# Mach_dieu_khien_tu_xa.net
KiCad netlist of a schematic drawn in Altium Designer
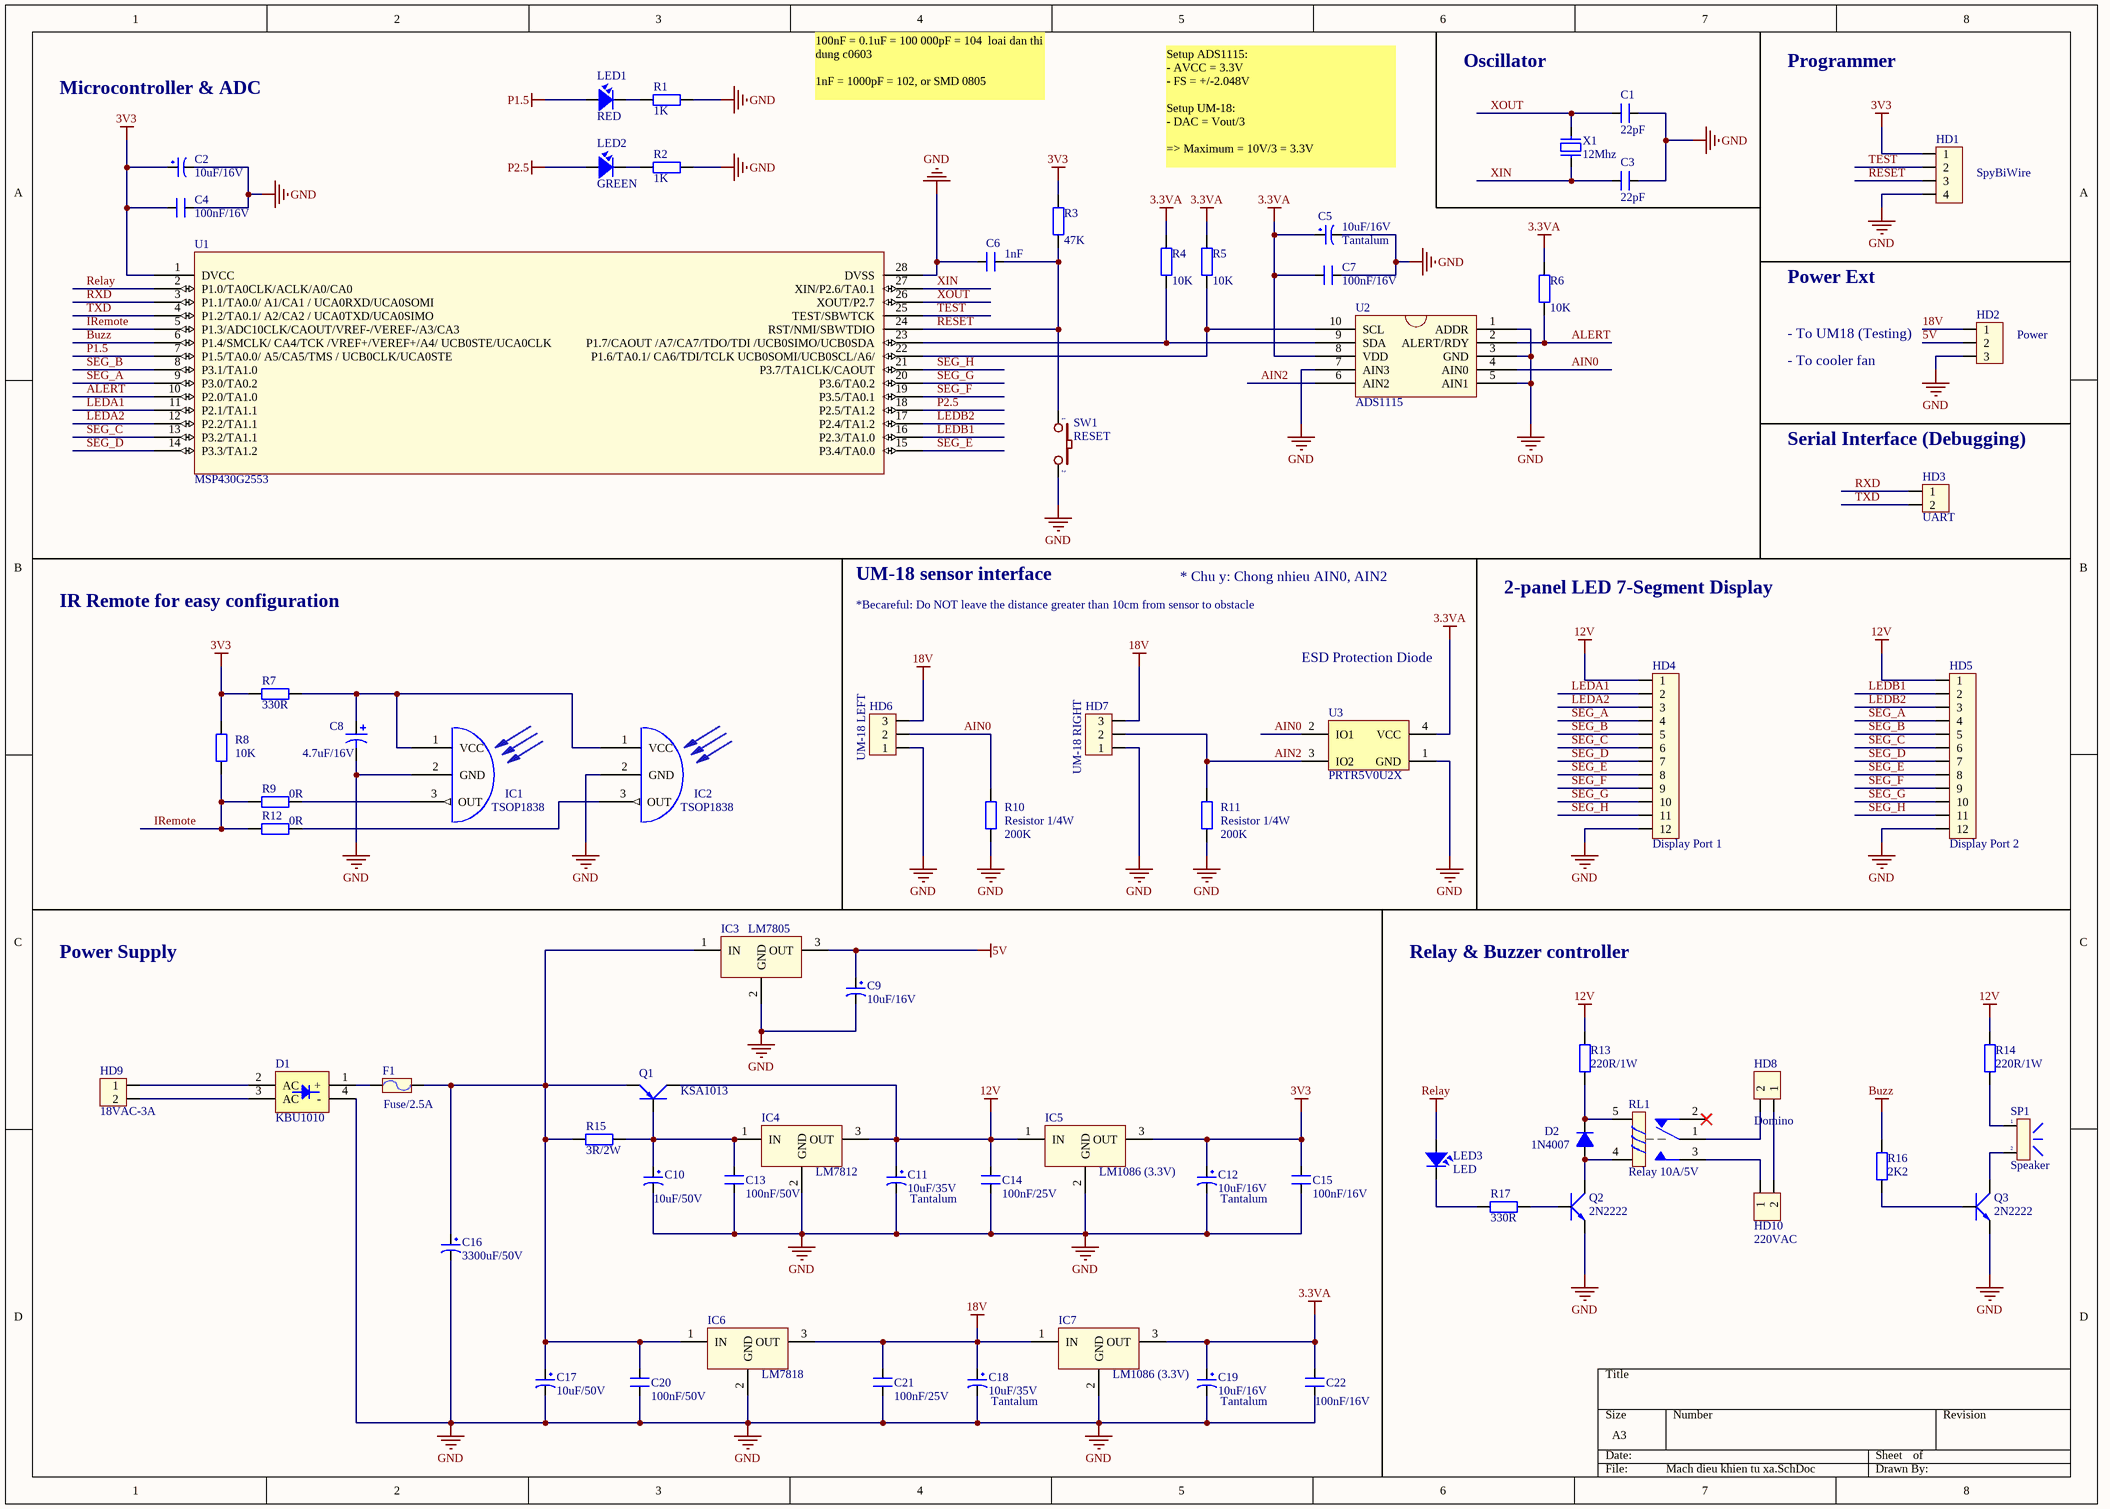
[diagram p0: Mach dieu khien tu xa.SchDoc]

(export (version "E")
  (design (tool "Eeschema 10.0.6"))
  (components
    (comp (ref "C1")
      (value "22pF")
      (footprint "C0603")
      (description "0805-SMD Capacitor")
      (libsource (lib "syhaunguyen") (part "CN1"))
    )
    (comp (ref "C2")
      (value "10uF/16V")
      (footprint "C0805")
      (description "Cap P  0,1uF < 22uF , 16 - 50V")
      (libsource (lib "") (part "CP1_1"))
    )
    (comp (ref "C3")
      (value "22pF")
      (footprint "C0603")
      (description "0805-SMD Capacitor")
      (libsource (lib "syhaunguyen") (part "CN1"))
    )
    (comp (ref "C4")
      (value "100nF/16V")
      (footprint "Tu gom 104")
      (description "Cap np 104 => 105pF")
      (libsource (lib "VNELEK") (part "CN2"))
    )
    (comp (ref "C5")
      (value "10uF/16V")
      (footprint "CAP_TANTA_10UF_16V")
      (description "Tantalum Capacitor")
      (fields (field (name "TYPE") "Tantalum"))
      (libsource (lib "") (part "CP1_1"))
    )
    (comp (ref "C6")
      (value "1nF")
      (footprint "C0805")
      (description "Cap np 104 => 105pF")
      (libsource (lib "VNELEK") (part "CN2"))
    )
    (comp (ref "C7")
      (value "100nF/16V")
      (footprint "Tu gom 104")
      (description "Cap np 104 => 105pF")
      (libsource (lib "VNELEK") (part "CN2"))
    )
    (comp (ref "C8")
      (value "4.7uF/16V")
      (footprint "C0805")
      (description "Polarized Capacitor (Radial)")
      (fields (field (name "Comment") "Cap Pol1") (field (name "PUBLISHER") "Altium Limited"))
      (libsource (lib "Miscellaneous Devices") (part "Cap Pol1"))
    )
    (comp (ref "C9")
      (value "10uF/16V")
      (footprint "CAP_10UF_16V")
      (description "Aluminium Capacitor")
      (libsource (lib "VNELEK") (part "CP1"))
    )
    (comp (ref "C10")
      (value "10uF/50V")
      (footprint "C_FC_10UF_50V")
      (description "Aluminium Capacitor")
      (libsource (lib "VNELEK") (part "CP1"))
    )
    (comp (ref "C11")
      (value "10uF/35V")
      (footprint "CAP_TANTA_10UF_35V")
      (description "Tantalum Capacitor")
      (fields (field (name "TYPE") "Tantalum"))
      (libsource (lib "VNELEK") (part "CP1"))
    )
    (comp (ref "C12")
      (value "10uF/16V")
      (footprint "CAP_TANTA_10UF_16V")
      (description "Tantalum Capacitor")
      (fields (field (name "TYPE") "Tantalum"))
      (libsource (lib "VNELEK") (part "CP1"))
    )
    (comp (ref "C13")
      (value "100nF/50V")
      (footprint "Tu gom 104")
      (description "Cap np 104 => 105pF")
      (libsource (lib "VNELEK") (part "CN2"))
    )
    (comp (ref "C14")
      (value "100nF/25V")
      (footprint "Tu gom 104")
      (description "Cap np 104 => 105pF")
      (libsource (lib "VNELEK") (part "CN2"))
    )
    (comp (ref "C15")
      (value "100nF/16V")
      (footprint "Tu gom 104")
      (description "Cap np 104 => 105pF")
      (libsource (lib "VNELEK") (part "CN2"))
    )
    (comp (ref "C16")
      (value "3300uF/50V")
      (footprint "CAP_3300UF_50V")
      (description "Cap P  0,1uF < 22uF , 16 - 50V")
      (libsource (lib "VNELEK") (part "CP1"))
    )
    (comp (ref "C17")
      (value "10uF/50V")
      (footprint "C_FC_10UF_50V")
      (description "Aluminium Capacitor")
      (libsource (lib "VNELEK") (part "CP1"))
    )
    (comp (ref "C18")
      (value "10uF/35V")
      (footprint "CAP_TANTA_10UF_35V")
      (description "Tantalum Capacitor")
      (fields (field (name "TYPE") "Tantalum"))
      (libsource (lib "VNELEK") (part "CP1"))
    )
    (comp (ref "C19")
      (value "10uF/16V")
      (footprint "CAP_TANTA_10UF_16V")
      (description "Tantalum Capacitor")
      (fields (field (name "TYPE") "Tantalum"))
      (libsource (lib "VNELEK") (part "CP1"))
    )
    (comp (ref "C20")
      (value "100nF/50V")
      (footprint "Tu gom 104")
      (description "Cap np 104 => 105pF")
      (libsource (lib "VNELEK") (part "CN2"))
    )
    (comp (ref "C21")
      (value "100nF/25V")
      (footprint "Tu gom 104")
      (description "Cap np 104 => 105pF")
      (libsource (lib "VNELEK") (part "CN2"))
    )
    (comp (ref "C22")
      (value "100nF/16V")
      (footprint "Tu gom 104")
      (description "Cap np 104 => 105pF")
      (libsource (lib "VNELEK") (part "CN2"))
    )
    (comp (ref "D1")
      (value "KBU1010")
      (footprint "KBU1010G")
      (description "10A glass passivated bridge rectifier")
      (libsource (lib "Tran Tuan") (part "KBU1010"))
    )
    (comp (ref "D2")
      (value "1N4007")
      (footprint "1N4007")
      (description "Diode 1A")
      (libsource (lib "VNELEK") (part "D1A"))
    )
    (comp (ref "F1")
      (value "Fuse/2.5A")
      (footprint "FUSE2_5A")
      (description "Fuse")
      (fields (field (name "DESIGNED BY") "VanDungEvn"))
      (libsource (lib "VNELEK") (part "Fuse"))
    )
    (comp (ref "HD1")
      (value "SpyBiWire")
      (footprint "Header_4")
      (description "Header 4 (Green)")
      (libsource (lib "VNELEK") (part "Hed4"))
    )
    (comp (ref "HD2")
      (value "Power")
      (footprint "CON3")
      (description "Header 3 (Green)")
      (libsource (lib "") (part "Hed3_1"))
    )
    (comp (ref "HD3")
      (value "UART")
      (footprint "Header_2")
      (description "Header 2 (Green)")
      (libsource (lib "VNELEK") (part "Hed2"))
    )
    (comp (ref "HD4")
      (value "Display Port 1")
      (footprint "CON12")
      (description "Header 12")
      (libsource (lib "Tran Tuan") (part "Hed12"))
    )
    (comp (ref "HD5")
      (value "Display Port 2")
      (footprint "CON12")
      (description "Header 12")
      (libsource (lib "Tran Tuan") (part "Hed12"))
    )
    (comp (ref "HD6")
      (value "UM-18 LEFT")
      (footprint "CON3")
      (description "Header 3 (Green)")
      (libsource (lib "VNELEK") (part "Hed3"))
    )
    (comp (ref "HD7")
      (value "UM-18 RIGHT")
      (footprint "CON3")
      (description "Header 3 (Green)")
      (libsource (lib "VNELEK") (part "Hed3"))
    )
    (comp (ref "HD8")
      (value "Domino")
      (footprint "DOMINO2_GREEN")
      (description "Header 2 (Green)")
      (libsource (lib "VNELEK") (part "Hed2"))
    )
    (comp (ref "HD9")
      (value "18VAC-3A")
      (footprint "DOMINO2_GREEN")
      (description "Header 2 (Green)")
      (libsource (lib "") (part "Hed2_2"))
    )
    (comp (ref "HD10")
      (value "220VAC")
      (footprint "DOMINO2_GREEN")
      (description "Header 2 (Green)")
      (libsource (lib "") (part "Hed2_1"))
    )
    (comp (ref "IC1")
      (value "TSOP1838")
      (footprint "TSOP1838")
      (libsource (lib "Tran Tuan") (part "TSOP1838"))
    )
    (comp (ref "IC2")
      (value "TSOP1838")
      (footprint "TSOP1838")
      (libsource (lib "Tran Tuan") (part "TSOP1838"))
    )
    (comp (ref "IC3")
      (value "LM7805")
      (footprint "LM7805")
      (description "Linear Regulator")
      (libsource (lib "VNELEK") (part "LM78xx"))
    )
    (comp (ref "IC4")
      (value "LM7812")
      (footprint "LM7805")
      (description "Linear Regulator")
      (fields (field (name "MANUFACTURER") "Fairchild Semiconductor"))
      (libsource (lib "VNELEK") (part "LM78xx"))
    )
    (comp (ref "IC5")
      (value "LM1086 (3.3V)")
      (footprint "LM1086")
      (description "Linear Regulator")
      (libsource (lib "VNELEK") (part "LM78xx"))
    )
    (comp (ref "IC6")
      (value "LM7818")
      (footprint "LM7805")
      (description "Linear Regulator")
      (libsource (lib "VNELEK") (part "LM78xx"))
    )
    (comp (ref "IC7")
      (value "LM1086 (3.3V)")
      (footprint "LM1086")
      (description "Linear Regulator")
      (libsource (lib "VNELEK") (part "LM78xx"))
    )
    (comp (ref "LED1")
      (value "RED")
      (footprint "LED3R")
      (description "LED Single colour Green and Red")
      (libsource (lib "VNELEK") (part "LED"))
    )
    (comp (ref "LED2")
      (value "GREEN")
      (footprint "LED3R")
      (description "LED Single colour Green and Red")
      (libsource (lib "VNELEK") (part "LED"))
    )
    (comp (ref "LED3")
      (value "LED")
      (footprint "LED3R")
      (description "LED Single colour Green and Red")
      (libsource (lib "VNELEK") (part "LED"))
    )
    (comp (ref "Q1")
      (value "KSA1013")
      (footprint "KSA1013")
      (description "PNP 600mW, ECB")
      (fields (field (name "MANUFACTURER") "Fairchild Semiconductor"))
      (libsource (lib "VNELEK") (part "A1015"))
    )
    (comp (ref "Q2")
      (value "2N2222")
      (footprint "2N2222")
      (description "TRANS GP SS NPN LP 40V TO92")
      (libsource (lib "VNELEK") (part "C1815"))
    )
    (comp (ref "Q3")
      (value "2N2222")
      (footprint "2N2222")
      (description "TRANS GP SS NPN LP 40V TO92")
      (libsource (lib "VNELEK") (part "C1815"))
    )
    (comp (ref "R1")
      (value "1K")
      (footprint "RESC2012(0805)")
      (description "Resistor")
      (fields (field (name "Comment") "Res2") (field (name "PUBLISHER") "Altium Limited"))
      (libsource (lib "") (part "Res2_1"))
    )
    (comp (ref "R2")
      (value "1K")
      (footprint "RESC2012(0805)")
      (description "Resistor")
      (fields (field (name "Comment") "Res2") (field (name "PUBLISHER") "Altium Limited"))
      (libsource (lib "") (part "Res2_1"))
    )
    (comp (ref "R3")
      (value "47K")
      (footprint "RESC2012(0805)")
      (description "Resistor")
      (fields (field (name "Comment") "Res2") (field (name "PUBLISHER") "Altium Limited"))
      (libsource (lib "Miscellaneous Devices") (part "Res2"))
    )
    (comp (ref "R4")
      (value "10K")
      (footprint "RESC2012(0805)")
      (description "Resistor")
      (fields (field (name "Comment") "Res2") (field (name "PUBLISHER") "Altium Limited"))
      (libsource (lib "Miscellaneous Devices") (part "Res2"))
    )
    (comp (ref "R5")
      (value "10K")
      (footprint "RESC2012(0805)")
      (description "Resistor")
      (fields (field (name "Comment") "Res2") (field (name "PUBLISHER") "Altium Limited"))
      (libsource (lib "Miscellaneous Devices") (part "Res2"))
    )
    (comp (ref "R6")
      (value "10K")
      (footprint "RESC2012(0805)")
      (description "Resistor")
      (fields (field (name "Comment") "Res2") (field (name "PUBLISHER") "Altium Limited"))
      (libsource (lib "Miscellaneous Devices") (part "Res2"))
    )
    (comp (ref "R7")
      (value "330R")
      (footprint "RESC2012(0805)")
      (description "Resistor")
      (fields (field (name "Comment") "Res2") (field (name "PUBLISHER") "Altium Limited"))
      (libsource (lib "") (part "Res2_1"))
    )
    (comp (ref "R8")
      (value "10K")
      (footprint "RESC2012(0805)")
      (description "Resistor")
      (fields (field (name "Comment") "Res2") (field (name "PUBLISHER") "Altium Limited"))
      (libsource (lib "Miscellaneous Devices") (part "Res2"))
    )
    (comp (ref "R9")
      (value "0R")
      (footprint "RESC2012(0805)")
      (description "Resistor")
      (fields (field (name "Comment") "Res2") (field (name "PUBLISHER") "Altium Limited"))
      (libsource (lib "") (part "Res2_1"))
    )
    (comp (ref "R10")
      (value "Resistor 1/4W")
      (footprint "RESC2012(0805)")
      (fields (field (name "ALTIUM_VALUE") "200K"))
      (libsource (lib "") (part "Res2_2"))
    )
    (comp (ref "R11")
      (value "Resistor 1/4W")
      (footprint "RESC2012(0805)")
      (fields (field (name "ALTIUM_VALUE") "200K"))
      (libsource (lib "") (part "Res2_2"))
    )
    (comp (ref "R12")
      (value "0R")
      (footprint "RESC2012(0805)")
      (description "Resistor")
      (fields (field (name "Comment") "Res2") (field (name "PUBLISHER") "Altium Limited"))
      (libsource (lib "") (part "Res2_1"))
    )
    (comp (ref "R13")
      (value "220R/1W")
      (footprint "CFR1WS")
      (description "Resistor")
      (fields (field (name "Comment") "Res2") (field (name "PUBLISHER") "Altium Limited"))
      (libsource (lib "") (part "Res2_2"))
    )
    (comp (ref "R14")
      (value "220R/1W")
      (footprint "CFR1WS")
      (description "Resistor")
      (fields (field (name "Comment") "Res2") (field (name "PUBLISHER") "Altium Limited"))
      (libsource (lib "") (part "Res2_2"))
    )
    (comp (ref "R15")
      (value "3R/2W")
      (footprint "R2WD")
      (description "Resistor")
      (fields (field (name "Comment") "Res2") (field (name "PUBLISHER") "Altium Limited"))
      (libsource (lib "") (part "Res2_1"))
    )
    (comp (ref "R16")
      (value "2K2")
      (footprint "RES 1/4W CFR25")
      (description "Resistor")
      (fields (field (name "Comment") "Res2") (field (name "PUBLISHER") "Altium Limited"))
      (libsource (lib "") (part "Res2_2"))
    )
    (comp (ref "R17")
      (value "330R")
      (footprint "RES 1/4W CFR25")
      (description "Resistor")
      (fields (field (name "Comment") "Res2") (field (name "PUBLISHER") "Altium Limited"))
      (libsource (lib "") (part "Res2_1"))
    )
    (comp (ref "RL1")
      (value "Relay 10A/5V")
      (footprint "RL_10A_5V")
      (description "Relay SPDT,10A - 12VDC 5 Pin")
      (libsource (lib "VNELEK") (part "Relay 1"))
    )
    (comp (ref "SP1")
      (value "Speaker")
      (footprint "SPEAKER")
      (description "Speaker Chip")
      (libsource (lib "VNELEK") (part "SPK"))
    )
    (comp (ref "SW1")
      (value "RESET")
      (footprint "BUTTON 2PIN TRON")
      (description "Switch button 2 pin")
      (libsource (lib "VNELEK") (part "SW2"))
    )
    (comp (ref "U1")
      (value "MSP430G2553")
      (footprint "MSP430G2253IPW28R")
      (description "MSP430G2553 (28 pins)")
      (libsource (lib "Tran Tuan") (part "MSP430G2553"))
    )
    (comp (ref "U2")
      (value "ADS1115")
      (footprint "ADS1115")
      (description "Analog to Digital Converter")
      (libsource (lib "Tran Tuan") (part "ADS1115"))
    )
    (comp (ref "U3")
      (value "PRTR5V0U2X")
      (footprint "PRTR5V0U2X")
      (description "ESD protection diode")
      (libsource (lib "Tran Tuan") (part "PRTR5V0U2X"))
    )
    (comp (ref "X1")
      (value "12Mhz")
      (footprint "CRYSTAL")
      (description "Crystal For all Crystal 2pin.")
      (libsource (lib "syhaunguyen") (part "XT2"))
    )
  )
  (nets
    (net (code "1") (name "/AIN0") (class "Default")
      (node (ref "HD6") (pin "2") (pinfunction "2_2") (pintype "passive"))
      (node (ref "R10") (pin "1") (pinfunction "1_1") (pintype "passive"))
      (node (ref "U2") (pin "4") (pinfunction "AIN0_4") (pintype "passive"))
      (node (ref "U3") (pin "2") (pinfunction "IO1_2") (pintype "passive"))
    )
    (net (code "2") (name "/AIN2") (class "Default")
      (node (ref "HD7") (pin "2") (pinfunction "2_2") (pintype "passive"))
      (node (ref "R11") (pin "1") (pinfunction "1_1") (pintype "passive"))
      (node (ref "U2") (pin "6") (pinfunction "AIN2_6") (pintype "passive"))
      (node (ref "U3") (pin "3") (pinfunction "IO2_3") (pintype "passive"))
    )
    (net (code "3") (name "/ALERT") (class "Default")
      (node (ref "R6") (pin "1") (pinfunction "1_1") (pintype "passive"))
      (node (ref "U1") (pin "10") (pinfunction "P2.0/TA1.0_10") (pintype "bidirectional"))
      (node (ref "U2") (pin "2") (pinfunction "ALERT/RDY_2") (pintype "passive"))
    )
    (net (code "4") (name "/IRemote") (class "Default")
      (node (ref "R12") (pin "2") (pinfunction "2_2") (pintype "passive"))
      (node (ref "R8") (pin "1") (pinfunction "1_1") (pintype "passive"))
      (node (ref "R9") (pin "2") (pinfunction "2_2") (pintype "passive"))
      (node (ref "U1") (pin "5") (pinfunction "P1.3/ADC10CLK/CAOUT/VREF-/VEREF-/A3/CA3_5") (pintype "bidirectional"))
    )
    (net (code "5") (name "/LEDA1") (class "Default")
      (node (ref "HD4") (pin "2") (pinfunction "2_2") (pintype "passive"))
      (node (ref "U1") (pin "11") (pinfunction "P2.1/TA1.1_11") (pintype "bidirectional"))
    )
    (net (code "6") (name "/LEDA2") (class "Default")
      (node (ref "HD4") (pin "3") (pinfunction "3_3") (pintype "passive"))
      (node (ref "U1") (pin "12") (pinfunction "P2.2/TA1.1_12") (pintype "bidirectional"))
    )
    (net (code "7") (name "/LEDB1") (class "Default")
      (node (ref "HD5") (pin "2") (pinfunction "2_2") (pintype "passive"))
      (node (ref "U1") (pin "16") (pinfunction "P2.3/TA1.0_16") (pintype "bidirectional"))
    )
    (net (code "8") (name "/LEDB2") (class "Default")
      (node (ref "HD5") (pin "3") (pinfunction "3_3") (pintype "passive"))
      (node (ref "U1") (pin "17") (pinfunction "P2.4/TA1.2_17") (pintype "bidirectional"))
    )
    (net (code "9") (name "/RESET") (class "Default")
      (node (ref "C6") (pin "2") (pinfunction "2_2") (pintype "passive"))
      (node (ref "HD1") (pin "3") (pinfunction "3_3") (pintype "passive"))
      (node (ref "R3") (pin "1") (pinfunction "1_1") (pintype "passive"))
      (node (ref "SW1") (pin "1") (pinfunction "1_1") (pintype "passive"))
      (node (ref "U1") (pin "24") (pinfunction "RST/NMI/SBWTDIO_24") (pintype "passive"))
    )
    (net (code "10") (name "/RXD") (class "Default")
      (node (ref "HD3") (pin "1") (pinfunction "1_1") (pintype "passive"))
      (node (ref "U1") (pin "3") (pinfunction "P1.1/TA0.0/_A1/CA1_/_UCA0RXD/UCA0SOMI_3") (pintype "bidirectional"))
    )
    (net (code "11") (name "/SEG_A") (class "Default")
      (node (ref "HD4") (pin "4") (pinfunction "4_4") (pintype "passive"))
      (node (ref "HD5") (pin "4") (pinfunction "4_4") (pintype "passive"))
      (node (ref "U1") (pin "9") (pinfunction "P3.0/TA0.2_9") (pintype "bidirectional"))
    )
    (net (code "12") (name "/SEG_B") (class "Default")
      (node (ref "HD4") (pin "5") (pinfunction "5_5") (pintype "passive"))
      (node (ref "HD5") (pin "5") (pinfunction "5_5") (pintype "passive"))
      (node (ref "U1") (pin "8") (pinfunction "P3.1/TA1.0_8") (pintype "bidirectional"))
    )
    (net (code "13") (name "/SEG_C") (class "Default")
      (node (ref "HD4") (pin "6") (pinfunction "6_6") (pintype "passive"))
      (node (ref "HD5") (pin "6") (pinfunction "6_6") (pintype "passive"))
      (node (ref "U1") (pin "13") (pinfunction "P3.2/TA1.1_13") (pintype "bidirectional"))
    )
    (net (code "14") (name "/SEG_D") (class "Default")
      (node (ref "HD4") (pin "7") (pinfunction "7_7") (pintype "passive"))
      (node (ref "HD5") (pin "7") (pinfunction "7_7") (pintype "passive"))
      (node (ref "U1") (pin "14") (pinfunction "P3.3/TA1.2_14") (pintype "bidirectional"))
    )
    (net (code "15") (name "/SEG_E") (class "Default")
      (node (ref "HD4") (pin "8") (pinfunction "8_8") (pintype "passive"))
      (node (ref "HD5") (pin "8") (pinfunction "8_8") (pintype "passive"))
      (node (ref "U1") (pin "15") (pinfunction "P3.4/TA0.0_15") (pintype "bidirectional"))
    )
    (net (code "16") (name "/SEG_F") (class "Default")
      (node (ref "HD4") (pin "9") (pinfunction "9_9") (pintype "passive"))
      (node (ref "HD5") (pin "9") (pinfunction "9_9") (pintype "passive"))
      (node (ref "U1") (pin "19") (pinfunction "P3.5/TA0.1_19") (pintype "bidirectional"))
    )
    (net (code "17") (name "/SEG_G") (class "Default")
      (node (ref "HD4") (pin "10") (pinfunction "10_10") (pintype "passive"))
      (node (ref "HD5") (pin "10") (pinfunction "10_10") (pintype "passive"))
      (node (ref "U1") (pin "20") (pinfunction "P3.6/TA0.2_20") (pintype "bidirectional"))
    )
    (net (code "18") (name "/SEG_H") (class "Default")
      (node (ref "HD4") (pin "11") (pinfunction "11_11") (pintype "passive"))
      (node (ref "HD5") (pin "11") (pinfunction "11_11") (pintype "passive"))
      (node (ref "U1") (pin "21") (pinfunction "P3.7/TA1CLK/CAOUT_21") (pintype "bidirectional"))
    )
    (net (code "19") (name "/TEST") (class "Default")
      (node (ref "HD1") (pin "2") (pinfunction "2_2") (pintype "passive"))
      (node (ref "U1") (pin "25") (pinfunction "TEST/SBWTCK_25") (pintype "passive"))
    )
    (net (code "20") (name "/TXD") (class "Default")
      (node (ref "HD3") (pin "2") (pinfunction "2_2") (pintype "passive"))
      (node (ref "U1") (pin "4") (pinfunction "P1.2/TA0.1/_A2/CA2_/_UCA0TXD/UCA0SIMO_4") (pintype "bidirectional"))
    )
    (net (code "21") (name "/XIN") (class "Default")
      (node (ref "C3") (pin "2") (pinfunction "2_2") (pintype "passive"))
      (node (ref "U1") (pin "27") (pinfunction "XIN/P2.6/TA0.1_27") (pintype "bidirectional"))
      (node (ref "X1") (pin "2") (pinfunction "2_2") (pintype "passive"))
    )
    (net (code "22") (name "/XOUT") (class "Default")
      (node (ref "C1") (pin "2") (pinfunction "2_2") (pintype "passive"))
      (node (ref "U1") (pin "26") (pinfunction "XOUT/P2.7_26") (pintype "bidirectional"))
      (node (ref "X1") (pin "1") (pinfunction "1_1") (pintype "passive"))
    )
    (net (code "23") (name "3.3VA") (class "Default")
      (node (ref "C19") (pin "1") (pinfunction "1_1") (pintype "passive"))
      (node (ref "C22") (pin "2") (pinfunction "2_2") (pintype "passive"))
      (node (ref "C5") (pin "1") (pinfunction "1_1") (pintype "passive"))
      (node (ref "C7") (pin "2") (pinfunction "2_2") (pintype "passive"))
      (node (ref "IC7") (pin "3") (pinfunction "OUT_3") (pintype "passive"))
      (node (ref "R4") (pin "2") (pinfunction "2_2") (pintype "passive"))
      (node (ref "R5") (pin "2") (pinfunction "2_2") (pintype "passive"))
      (node (ref "R6") (pin "2") (pinfunction "2_2") (pintype "passive"))
      (node (ref "U2") (pin "8") (pinfunction "VDD_8") (pintype "passive"))
      (node (ref "U3") (pin "4") (pinfunction "VCC_4") (pintype "passive"))
    )
    (net (code "24") (name "3V3") (class "Default")
      (node (ref "C12") (pin "1") (pinfunction "1_1") (pintype "passive"))
      (node (ref "C15") (pin "2") (pinfunction "2_2") (pintype "passive"))
      (node (ref "C2") (pin "1") (pinfunction "1_1") (pintype "passive"))
      (node (ref "C4") (pin "2") (pinfunction "2_2") (pintype "passive"))
      (node (ref "HD1") (pin "1") (pinfunction "1_1") (pintype "passive"))
      (node (ref "IC5") (pin "3") (pinfunction "OUT_3") (pintype "passive"))
      (node (ref "R3") (pin "2") (pinfunction "2_2") (pintype "passive"))
      (node (ref "R7") (pin "2") (pinfunction "2_2") (pintype "passive"))
      (node (ref "R8") (pin "2") (pinfunction "2_2") (pintype "passive"))
      (node (ref "U1") (pin "1") (pinfunction "DVCC_1") (pintype "power_in"))
    )
    (net (code "25") (name "5V") (class "Default")
      (node (ref "C9") (pin "1") (pinfunction "1_1") (pintype "passive"))
      (node (ref "HD2") (pin "2") (pinfunction "2_2") (pintype "passive"))
      (node (ref "IC3") (pin "3") (pinfunction "OUT_3") (pintype "passive"))
    )
    (net (code "26") (name "12V") (class "Default")
      (node (ref "C11") (pin "1") (pinfunction "1_1") (pintype "passive"))
      (node (ref "C14") (pin "2") (pinfunction "2_2") (pintype "passive"))
      (node (ref "HD4") (pin "1") (pinfunction "1_1") (pintype "passive"))
      (node (ref "HD5") (pin "1") (pinfunction "1_1") (pintype "passive"))
      (node (ref "IC4") (pin "3") (pinfunction "OUT_3") (pintype "passive"))
      (node (ref "IC5") (pin "1") (pinfunction "IN_1") (pintype "passive"))
      (node (ref "Q1") (pin "2") (pinfunction "C_2") (pintype "passive"))
      (node (ref "R13") (pin "1") (pinfunction "1_1") (pintype "passive"))
      (node (ref "R14") (pin "1") (pinfunction "1_1") (pintype "passive"))
    )
    (net (code "27") (name "18V") (class "Default")
      (node (ref "C18") (pin "1") (pinfunction "1_1") (pintype "passive"))
      (node (ref "C21") (pin "2") (pinfunction "2_2") (pintype "passive"))
      (node (ref "HD2") (pin "1") (pinfunction "1_1") (pintype "passive"))
      (node (ref "HD6") (pin "3") (pinfunction "3_3") (pintype "passive"))
      (node (ref "HD7") (pin "3") (pinfunction "3_3") (pintype "passive"))
      (node (ref "IC6") (pin "3") (pinfunction "OUT_3") (pintype "passive"))
      (node (ref "IC7") (pin "1") (pinfunction "IN_1") (pintype "passive"))
    )
    (net (code "28") (name "Buzz") (class "Default")
      (node (ref "R16") (pin "1") (pinfunction "1_1") (pintype "passive"))
      (node (ref "U1") (pin "6") (pinfunction "P1.4/SMCLK/_CA4/TCK_/VREF+/VEREF+/A4/_UCB0STE/UCA0CLK_6") (pintype "bidirectional"))
    )
    (net (code "29") (name "GND") (class "Default")
      (node (ref "C1") (pin "1") (pinfunction "1_1") (pintype "passive"))
      (node (ref "C10") (pin "2") (pinfunction "2_2") (pintype "passive"))
      (node (ref "C11") (pin "2") (pinfunction "2_2") (pintype "passive"))
      (node (ref "C12") (pin "2") (pinfunction "2_2") (pintype "passive"))
      (node (ref "C13") (pin "1") (pinfunction "1_1") (pintype "passive"))
      (node (ref "C14") (pin "1") (pinfunction "1_1") (pintype "passive"))
      (node (ref "C15") (pin "1") (pinfunction "1_1") (pintype "passive"))
      (node (ref "C16") (pin "2") (pinfunction "2_2") (pintype "passive"))
      (node (ref "C17") (pin "2") (pinfunction "2_2") (pintype "passive"))
      (node (ref "C18") (pin "2") (pinfunction "2_2") (pintype "passive"))
      (node (ref "C19") (pin "2") (pinfunction "2_2") (pintype "passive"))
      (node (ref "C2") (pin "2") (pinfunction "2_2") (pintype "passive"))
      (node (ref "C20") (pin "1") (pinfunction "1_1") (pintype "passive"))
      (node (ref "C21") (pin "1") (pinfunction "1_1") (pintype "passive"))
      (node (ref "C22") (pin "1") (pinfunction "1_1") (pintype "passive"))
      (node (ref "C3") (pin "1") (pinfunction "1_1") (pintype "passive"))
      (node (ref "C4") (pin "1") (pinfunction "1_1") (pintype "passive"))
      (node (ref "C5") (pin "2") (pinfunction "2_2") (pintype "passive"))
      (node (ref "C6") (pin "1") (pinfunction "1_1") (pintype "passive"))
      (node (ref "C7") (pin "1") (pinfunction "1_1") (pintype "passive"))
      (node (ref "C8") (pin "2") (pinfunction "2_2") (pintype "passive"))
      (node (ref "C9") (pin "2") (pinfunction "2_2") (pintype "passive"))
      (node (ref "D1") (pin "4") (pinfunction "-_4") (pintype "power_in"))
      (node (ref "HD1") (pin "4") (pinfunction "4_4") (pintype "passive"))
      (node (ref "HD2") (pin "3") (pinfunction "3_3") (pintype "passive"))
      (node (ref "HD4") (pin "12") (pinfunction "12_12") (pintype "passive"))
      (node (ref "HD5") (pin "12") (pinfunction "12_12") (pintype "passive"))
      (node (ref "HD6") (pin "1") (pinfunction "1_1") (pintype "passive"))
      (node (ref "HD7") (pin "1") (pinfunction "1_1") (pintype "passive"))
      (node (ref "IC1") (pin "2") (pinfunction "GND_2") (pintype "power_in"))
      (node (ref "IC2") (pin "2") (pinfunction "GND_2") (pintype "power_in"))
      (node (ref "IC3") (pin "2") (pinfunction "GND_2") (pintype "passive"))
      (node (ref "IC4") (pin "2") (pinfunction "GND_2") (pintype "passive"))
      (node (ref "IC5") (pin "2") (pinfunction "GND_2") (pintype "passive"))
      (node (ref "IC6") (pin "2") (pinfunction "GND_2") (pintype "passive"))
      (node (ref "IC7") (pin "2") (pinfunction "GND_2") (pintype "passive"))
      (node (ref "Q2") (pin "1") (pinfunction "E_1") (pintype "passive"))
      (node (ref "Q3") (pin "1") (pinfunction "E_1") (pintype "passive"))
      (node (ref "R1") (pin "1") (pinfunction "1_1") (pintype "passive"))
      (node (ref "R10") (pin "2") (pinfunction "2_2") (pintype "passive"))
      (node (ref "R11") (pin "2") (pinfunction "2_2") (pintype "passive"))
      (node (ref "R2") (pin "1") (pinfunction "1_1") (pintype "passive"))
      (node (ref "SW1") (pin "2") (pinfunction "2_2") (pintype "passive"))
      (node (ref "U1") (pin "28") (pinfunction "DVSS_28") (pintype "passive"))
      (node (ref "U2") (pin "1") (pinfunction "ADDR_1") (pintype "passive"))
      (node (ref "U2") (pin "3") (pinfunction "GND_3") (pintype "passive"))
      (node (ref "U2") (pin "5") (pinfunction "AIN1_5") (pintype "passive"))
      (node (ref "U2") (pin "7") (pinfunction "AIN3_7") (pintype "passive"))
      (node (ref "U3") (pin "1") (pinfunction "GND_1") (pintype "passive"))
    )
    (net (code "30") (name "Net-(D1-+)") (class "Default")
      (node (ref "D1") (pin "1") (pinfunction "+_1") (pintype "power_in"))
      (node (ref "F1") (pin "1") (pinfunction "1_1") (pintype "passive"))
    )
    (net (code "31") (name "Net-(D1-AC-Pad2)") (class "Default")
      (node (ref "D1") (pin "2") (pinfunction "AC_2") (pintype "power_in"))
      (node (ref "HD9") (pin "1") (pinfunction "1_1") (pintype "passive"))
    )
    (net (code "32") (name "Net-(D1-AC-Pad3)") (class "Default")
      (node (ref "D1") (pin "3") (pinfunction "AC_3") (pintype "power_in"))
      (node (ref "HD9") (pin "2") (pinfunction "2_2") (pintype "passive"))
    )
    (net (code "33") (name "Net-(D2-A)") (class "Default")
      (node (ref "D2") (pin "1") (pinfunction "A_1") (pintype "passive"))
      (node (ref "Q2") (pin "3") (pinfunction "C_3") (pintype "passive"))
      (node (ref "RL1") (pin "4") (pinfunction "4_4") (pintype "passive"))
    )
    (net (code "34") (name "Net-(D2-K)") (class "Default")
      (node (ref "D2") (pin "2") (pinfunction "K_2") (pintype "passive"))
      (node (ref "R13") (pin "2") (pinfunction "2_2") (pintype "passive"))
      (node (ref "RL1") (pin "5") (pinfunction "5_5") (pintype "passive"))
    )
    (net (code "35") (name "Net-(HD8-Pad2)") (class "Default")
      (node (ref "HD8") (pin "2") (pinfunction "2_2") (pintype "passive"))
      (node (ref "RL1") (pin "1") (pinfunction "1_1") (pintype "passive"))
    )
    (net (code "36") (name "Net-(HD10-Pad1)") (class "Default")
      (node (ref "HD10") (pin "1") (pinfunction "1_1") (pintype "passive"))
      (node (ref "RL1") (pin "3") (pinfunction "3_3") (pintype "passive"))
    )
    (net (code "37") (name "Net-(HD10-Pad2)") (class "Default")
      (node (ref "HD10") (pin "2") (pinfunction "2_2") (pintype "passive"))
      (node (ref "HD8") (pin "1") (pinfunction "1_1") (pintype "passive"))
    )
    (net (code "38") (name "Net-(IC1-OUT)") (class "Default")
      (node (ref "IC1") (pin "3") (pinfunction "OUT_3") (pintype "output"))
      (node (ref "R9") (pin "1") (pinfunction "1_1") (pintype "passive"))
    )
    (net (code "39") (name "Net-(IC1-VCC)") (class "Default")
      (node (ref "C8") (pin "1") (pinfunction "1_1") (pintype "passive"))
      (node (ref "IC1") (pin "1") (pinfunction "VCC_1") (pintype "power_in"))
      (node (ref "IC2") (pin "1") (pinfunction "VCC_1") (pintype "power_in"))
      (node (ref "R7") (pin "1") (pinfunction "1_1") (pintype "passive"))
    )
    (net (code "40") (name "Net-(IC2-OUT)") (class "Default")
      (node (ref "IC2") (pin "3") (pinfunction "OUT_3") (pintype "output"))
      (node (ref "R12") (pin "1") (pinfunction "1_1") (pintype "passive"))
    )
    (net (code "41") (name "Net-(IC3-IN)") (class "Default")
      (node (ref "C16") (pin "1") (pinfunction "1_1") (pintype "passive"))
      (node (ref "C17") (pin "1") (pinfunction "1_1") (pintype "passive"))
      (node (ref "C20") (pin "2") (pinfunction "2_2") (pintype "passive"))
      (node (ref "F1") (pin "2") (pinfunction "2_2") (pintype "passive"))
      (node (ref "IC3") (pin "1") (pinfunction "IN_1") (pintype "passive"))
      (node (ref "IC6") (pin "1") (pinfunction "IN_1") (pintype "passive"))
      (node (ref "Q1") (pin "1") (pinfunction "E_1") (pintype "passive"))
      (node (ref "R15") (pin "2") (pinfunction "2_2") (pintype "passive"))
    )
    (net (code "42") (name "Net-(IC4-IN)") (class "Default")
      (node (ref "C10") (pin "1") (pinfunction "1_1") (pintype "passive"))
      (node (ref "C13") (pin "2") (pinfunction "2_2") (pintype "passive"))
      (node (ref "IC4") (pin "1") (pinfunction "IN_1") (pintype "passive"))
      (node (ref "Q1") (pin "3") (pinfunction "B_3") (pintype "passive"))
      (node (ref "R15") (pin "1") (pinfunction "1_1") (pintype "passive"))
    )
    (net (code "43") (name "Net-(LED1-Pad2)") (class "Default")
      (node (ref "LED1") (pin "2") (pinfunction "2_2") (pintype "passive"))
      (node (ref "R1") (pin "2") (pinfunction "2_2") (pintype "passive"))
    )
    (net (code "44") (name "Net-(LED2-Pad2)") (class "Default")
      (node (ref "LED2") (pin "2") (pinfunction "2_2") (pintype "passive"))
      (node (ref "R2") (pin "2") (pinfunction "2_2") (pintype "passive"))
    )
    (net (code "45") (name "Net-(LED3-Pad2)") (class "Default")
      (node (ref "LED3") (pin "2") (pinfunction "2_2") (pintype "passive"))
      (node (ref "R17") (pin "2") (pinfunction "2_2") (pintype "passive"))
    )
    (net (code "46") (name "Net-(Q2-B)") (class "Default")
      (node (ref "Q2") (pin "2") (pinfunction "B_2") (pintype "passive"))
      (node (ref "R17") (pin "1") (pinfunction "1_1") (pintype "passive"))
    )
    (net (code "47") (name "Net-(Q3-B)") (class "Default")
      (node (ref "Q3") (pin "2") (pinfunction "B_2") (pintype "passive"))
      (node (ref "R16") (pin "2") (pinfunction "2_2") (pintype "passive"))
    )
    (net (code "48") (name "Net-(Q3-C)") (class "Default")
      (node (ref "Q3") (pin "3") (pinfunction "C_3") (pintype "passive"))
      (node (ref "SP1") (pin "2") (pinfunction "2_2") (pintype "passive"))
    )
    (net (code "49") (name "Net-(R14-Pad2)") (class "Default")
      (node (ref "R14") (pin "2") (pinfunction "2_2") (pintype "passive"))
      (node (ref "SP1") (pin "1") (pinfunction "1_1") (pintype "passive"))
    )
    (net (code "50") (name "Net-(U1-P1.6{slash}TA0.1{slash}_CA6{slash}TDI{slash}TCLK_UCB0SOMI{slash}UCB0SCL{slash}A6{slash})") (class "Default")
      (node (ref "R5") (pin "1") (pinfunction "1_1") (pintype "passive"))
      (node (ref "U1") (pin "22") (pinfunction "P1.6/TA0.1/_CA6/TDI/TCLK_UCB0SOMI/UCB0SCL/A6/_22") (pintype "bidirectional"))
      (node (ref "U2") (pin "10") (pinfunction "SCL_10") (pintype "passive"))
    )
    (net (code "51") (name "Net-(U1-P1.7{slash}CAOUT_{slash}A7{slash}CA7{slash}TDO{slash}TDI_{slash}UCB0SIMO{slash}UCB0SDA)") (class "Default")
      (node (ref "R4") (pin "1") (pinfunction "1_1") (pintype "passive"))
      (node (ref "U1") (pin "23") (pinfunction "P1.7/CAOUT_/A7/CA7/TDO/TDI_/UCB0SIMO/UCB0SDA_23") (pintype "bidirectional"))
      (node (ref "U2") (pin "9") (pinfunction "SDA_9") (pintype "passive"))
    )
    (net (code "52") (name "P1.5") (class "Default")
      (node (ref "LED1") (pin "1") (pinfunction "1_1") (pintype "passive"))
      (node (ref "U1") (pin "7") (pinfunction "P1.5/TA0.0/_A5/CA5/TMS_/_UCB0CLK/UCA0STE_7") (pintype "bidirectional"))
    )
    (net (code "53") (name "P2.5") (class "Default")
      (node (ref "LED2") (pin "1") (pinfunction "1_1") (pintype "passive"))
      (node (ref "U1") (pin "18") (pinfunction "P2.5/TA1.2_18") (pintype "bidirectional"))
    )
    (net (code "54") (name "Relay") (class "Default")
      (node (ref "LED3") (pin "1") (pinfunction "1_1") (pintype "passive"))
      (node (ref "U1") (pin "2") (pinfunction "P1.0/TA0CLK/ACLK/A0/CA0_2") (pintype "bidirectional"))
    )
    (net (code "55") (name "unconnected-(RL1-Pad2)") (class "Default")
      (node (ref "RL1") (pin "2") (pinfunction "2_2") (pintype "passive+no_connect"))
    )
  )
)
